# WiFan.net
KiCad netlist of a schematic drawn in Altium Designer
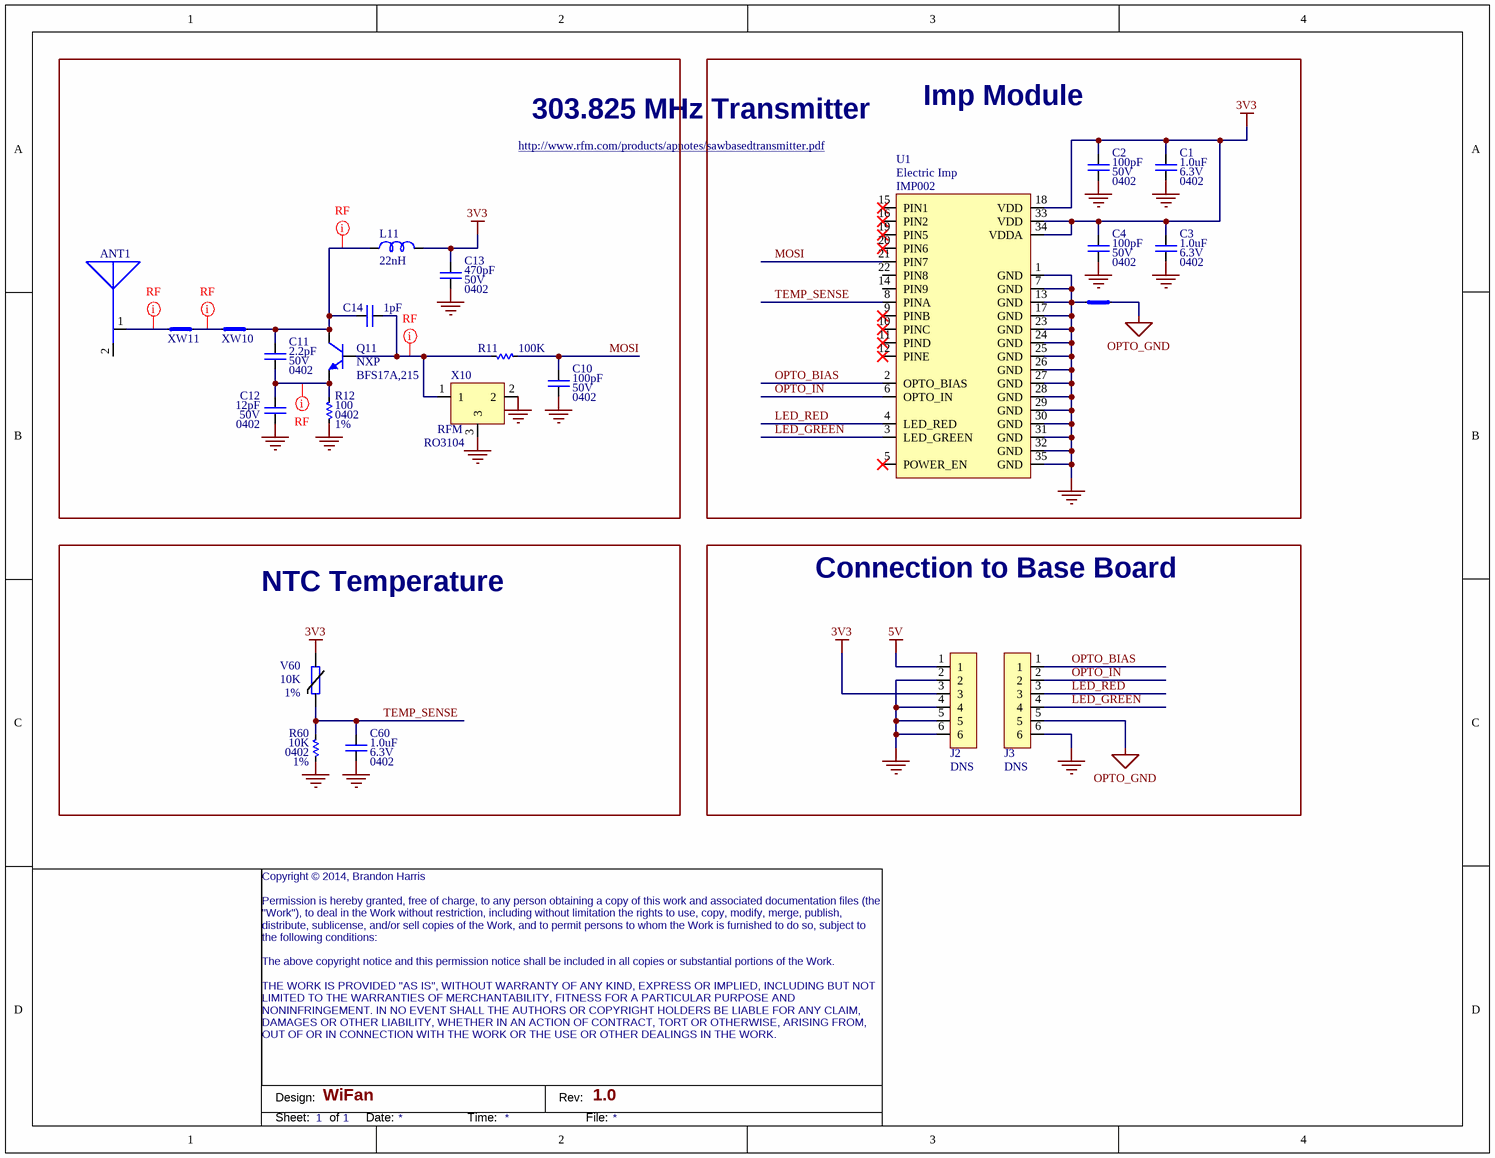
[diagram p0: WiFan.SchDoc]

(export (version "E")
  (design (tool "Eeschema 10.0.6"))
  (components
    (comp (ref "ANT1")
      (value "ANT")
      (footprint "ANT-433-HETH")
      (description "Antenna, 433 MHz, through-hole, helical, air core")
      (fields (field (name "PART NUMBER") "ANT00001") (field (name "MANUFACTURER") "Linx Technologies"))
      (libsource (lib "electromechanical") (part "ANT"))
    )
    (comp (ref "C1")
      (value "1.0uF")
      (footprint "CAPC1005X07N")
      (description "CAP,X5R,1.0uF,10%,6.3V, 0402,#")
      (fields
        (field (name "TOLERANCE") "10%")
        (field (name "VOLTAGE") "6.3V")
        (field (name "PACKAGE") "0402")
        (field (name "PART NUMBER") "CAPC00005")
      )
      (libsource (lib "passives") (part "CAPC"))
    )
    (comp (ref "C2")
      (value "100pF")
      (footprint "CAPC1005X07N")
      (description "CAP,C0G,100pF,5%,50V,0402")
      (fields
        (field (name "TOLERANCE") "5%")
        (field (name "VOLTAGE") "50V")
        (field (name "PACKAGE") "0402")
        (field (name "PART NUMBER") "CAPC00043")
      )
      (libsource (lib "passives") (part "CAPC"))
    )
    (comp (ref "C3")
      (value "1.0uF")
      (footprint "CAPC1005X07N")
      (description "CAP,X5R,1.0uF,10%,6.3V, 0402,#")
      (fields
        (field (name "TOLERANCE") "10%")
        (field (name "VOLTAGE") "6.3V")
        (field (name "PACKAGE") "0402")
        (field (name "PART NUMBER") "CAPC00005")
      )
      (libsource (lib "passives") (part "CAPC"))
    )
    (comp (ref "C4")
      (value "100pF")
      (footprint "CAPC1005X07N")
      (description "CAP,C0G,100pF,5%,50V,0402")
      (fields
        (field (name "TOLERANCE") "5%")
        (field (name "VOLTAGE") "50V")
        (field (name "PACKAGE") "0402")
        (field (name "PART NUMBER") "CAPC00043")
      )
      (libsource (lib "passives") (part "CAPC"))
    )
    (comp (ref "C10")
      (value "100pF")
      (footprint "CAPC1005X07N")
      (description "CAP,C0G,100pF,5%,50V,0402")
      (fields
        (field (name "TOLERANCE") "5%")
        (field (name "VOLTAGE") "50V")
        (field (name "PACKAGE") "0402")
        (field (name "PART NUMBER") "CAPC00043")
      )
      (libsource (lib "passives") (part "CAPC"))
    )
    (comp (ref "C11")
      (value "2.2pF")
      (footprint "CAPC1005X07N")
      (description "CAP,C0G,2.2pF,+/-0.25pF,50V,0402")
      (fields
        (field (name "TOLERANCE") "0.25p")
        (field (name "VOLTAGE") "50V")
        (field (name "PACKAGE") "0402")
        (field (name "PART NUMBER") "CAPC00080")
      )
      (libsource (lib "passives") (part "CAPC"))
    )
    (comp (ref "C12")
      (value "12pF")
      (footprint "CAPC1005X07N")
      (description "CAP,C0G,12pF,5%,50V,0402#")
      (fields
        (field (name "TOLERANCE") "5%")
        (field (name "VOLTAGE") "50V")
        (field (name "PACKAGE") "0402")
        (field (name "PART NUMBER") "CAPC00041")
      )
      (libsource (lib "passives") (part "CAPC"))
    )
    (comp (ref "C13")
      (value "470pF")
      (footprint "CAPC1005X07N")
      (description "CAP,C0G,470pF,5%,50V,0402")
      (fields
        (field (name "TOLERANCE") "5%")
        (field (name "VOLTAGE") "50V")
        (field (name "PACKAGE") "0402")
        (field (name "PART NUMBER") "CAPC00047")
      )
      (libsource (lib "passives") (part "CAPC"))
    )
    (comp (ref "C14")
      (value "1pF")
      (footprint "CAPC1005X07N")
      (description "CAP,NPO,1pF, 0402, 50V")
      (fields (field (name "TOLERANCE") "0.25p") (field (name "VOLTAGE") "50V"))
      (libsource (lib "passives") (part "CAPC"))
    )
    (comp (ref "C60")
      (value "1.0uF")
      (footprint "CAPC1005X07N")
      (description "CAP,X5R,1.0uF,10%,6.3V, 0402,#")
      (fields
        (field (name "TOLERANCE") "10%")
        (field (name "VOLTAGE") "6.3V")
        (field (name "PACKAGE") "0402")
        (field (name "PART NUMBER") "CAPC00005")
      )
      (libsource (lib "passives") (part "CAPC"))
    )
    (comp (ref "J2")
      (value "Header")
      (footprint "HDR254P1X6-N:HDR254P1X6-N")
      (description "Spacer, 1x6 Pin, 2.54mm Pitch, 0.661\" Stack Height, Vertical, Through Hole")
      (fields
        (field (name "PART NUMBER") "HDR00020")
        (field (name "MANUFACTURER") "Harwin")
        (field (name "BOMOPTION") "DNS")
      )
      (libsource (lib "discretes") (part "HDR1X6"))
    )
    (comp (ref "J3")
      (value "Header")
      (footprint "HDR254P1X6-N:HDR254P1X6-N")
      (description "Spacer, 1x6 Pin, 2.54mm Pitch, 0.661\" Stack Height, Vertical, Through Hole")
      (fields
        (field (name "PART NUMBER") "HDR00020")
        (field (name "MANUFACTURER") "Harwin")
        (field (name "BOMOPTION") "DNS")
      )
      (libsource (lib "") (part "HDR1X6_1"))
    )
    (comp (ref "L11")
      (value "22nH")
      (footprint "INDC1005X06N")
      (description "IND, 22nH, 5%, 300mA, 600 mOhm, 0402")
      (fields (field (name "PART NUMBER") "IND00036") (field (name "TOLERANCE") "5%"))
      (libsource (lib "passives") (part "INDUCTOR"))
    )
    (comp (ref "Q11")
      (value "NPN Bipolar Transistor")
      (footprint "SOT95P300X130-3N")
      (description "NPN,15V, 25mA, 2.8GHz, SOT23")
      (fields
        (field (name "PART NUMBER") "NPN00003")
        (field (name "MANUFACTURER") "NXP")
        (field (name "MANUFACTURER PART NUMBER") "BFS17A,215")
      )
      (libsource (lib "discretes") (part "NPN"))
    )
    (comp (ref "R11")
      (value "100K")
      (footprint "RESC1005X04N")
      (description "RES,100k,5%,0.063W,0402,#")
      (fields (field (name "PART NUMBER") "RES00001") (field (name "TOLERANCE") "5%"))
      (libsource (lib "passives") (part "RES"))
    )
    (comp (ref "R12")
      (value "100")
      (footprint "RESC1005X04N")
      (description "RES,100 Ohm,1%,0.063W,0402,#")
      (fields
        (field (name "PART NUMBER") "RES00024")
        (field (name "PACKAGE") "0402")
        (field (name "TOLERANCE") "1%")
        (field (name "POWER") "0.063W")
      )
      (libsource (lib "passives") (part "RES"))
    )
    (comp (ref "R60")
      (value "10K")
      (footprint "RESC1005X04N")
      (description "RES,10K,1%,0.063W,0402,#")
      (fields
        (field (name "PART NUMBER") "RES00020")
        (field (name "PACKAGE") "0402")
        (field (name "TOLERANCE") "1%")
        (field (name "POWER") "0.063W")
      )
      (libsource (lib "passives") (part "RES"))
    )
    (comp (ref "U1")
      (value "imp module")
      (footprint "IMP_MODULE")
      (description "Module, Electric Imp Solder Down with Antenna")
      (fields
        (field (name "PART NUMBER") "MOD00002")
        (field (name "MANUFACTURER") "Electric Imp")
        (field (name "MANUFACTURER PART NUMBER") "IMP002")
      )
      (libsource (lib "modules") (part "IMP_MODULE"))
    )
    (comp (ref "V60")
      (value "10K")
      (footprint "HDR1X2")
      (description "Thermistor, NTC, 10K, 1%, Radial")
      (fields
        (field (name "PART NUMBER") "NTC00008")
        (field (name "MANUFACTURER") "Murata")
        (field (name "PRECISION") "1%")
      )
      (libsource (lib "passives") (part "VARISTOR"))
    )
    (comp (ref "X10")
      (value "RESONATOR-3N")
      (footprint "TO39-3")
      (description "Resonator,SAW,303.825MHz,TO39-3")
      (fields
        (field (name "PART NUMBER") "RESONATOR00001")
        (field (name "MANUFACTURER") "RFM")
        (field (name "MANUFACTURER PART NUMBER") "RO3104")
      )
      (libsource (lib "xtalosc") (part "RESONATOR-3N"))
    )
    (comp (ref "XW1")
      (value "XW Link")
      (footprint "XW1005-COVERED")
      (description "Short two wires together")
      (fields (field (name "PART NUMBER") "ELEC00008"))
      (libsource (lib "electrical") (part "XW"))
    )
    (comp (ref "XW10")
      (value "XW Link")
      (footprint "XW1005-UNCOVERED")
      (description "Short two wires together")
      (fields (field (name "PART NUMBER") "ELEC00007"))
      (libsource (lib "electrical") (part "XW"))
    )
    (comp (ref "XW11")
      (value "XW Link")
      (footprint "XW1005-UNCOVERED")
      (description "Short two wires together")
      (fields (field (name "PART NUMBER") "ELEC00007"))
      (libsource (lib "electrical") (part "XW"))
    )
  )
  (nets
    (net (code "1") (name "/LED_GREEN") (class "Default")
      (node (ref "J3") (pin "4") (pinfunction "4_4") (pintype "passive"))
      (node (ref "U1") (pin "3") (pinfunction "LED_GREEN_3") (pintype "passive"))
    )
    (net (code "2") (name "/LED_RED") (class "Default")
      (node (ref "J3") (pin "3") (pinfunction "3_3") (pintype "passive"))
      (node (ref "U1") (pin "4") (pinfunction "LED_RED_4") (pintype "passive"))
    )
    (net (code "3") (name "/MOSI") (class "Default")
      (node (ref "C10") (pin "2") (pinfunction "2_2") (pintype "passive"))
      (node (ref "R11") (pin "1") (pinfunction "1_1") (pintype "passive"))
      (node (ref "U1") (pin "21") (pinfunction "PIN7_21") (pintype "passive"))
    )
    (net (code "4") (name "/OPTO_BIAS") (class "Default")
      (node (ref "J3") (pin "1") (pinfunction "1_1") (pintype "passive"))
      (node (ref "U1") (pin "2") (pinfunction "OPTO_BIAS_2") (pintype "passive"))
    )
    (net (code "5") (name "/OPTO_IN") (class "Default")
      (node (ref "J3") (pin "2") (pinfunction "2_2") (pintype "passive"))
      (node (ref "U1") (pin "6") (pinfunction "OPTO_IN_6") (pintype "passive"))
    )
    (net (code "6") (name "/TEMP_SENSE") (class "Default")
      (node (ref "C60") (pin "2") (pinfunction "2_2") (pintype "passive"))
      (node (ref "R60") (pin "2") (pinfunction "2_2") (pintype "passive"))
      (node (ref "U1") (pin "8") (pinfunction "PINA_8") (pintype "passive"))
      (node (ref "V60") (pin "2") (pinfunction "2_2") (pintype "passive"))
    )
    (net (code "7") (name "3V3") (class "Default")
      (node (ref "C1") (pin "2") (pinfunction "2_2") (pintype "passive"))
      (node (ref "C13") (pin "2") (pinfunction "2_2") (pintype "passive"))
      (node (ref "C2") (pin "2") (pinfunction "2_2") (pintype "passive"))
      (node (ref "C3") (pin "2") (pinfunction "2_2") (pintype "passive"))
      (node (ref "C4") (pin "2") (pinfunction "2_2") (pintype "passive"))
      (node (ref "J2") (pin "3") (pinfunction "3_3") (pintype "passive"))
      (node (ref "L11") (pin "1") (pinfunction "1_1") (pintype "passive"))
      (node (ref "U1") (pin "18") (pinfunction "VDD_18") (pintype "passive"))
      (node (ref "U1") (pin "33") (pinfunction "VDD_33") (pintype "passive"))
      (node (ref "U1") (pin "34") (pinfunction "VDDA_34") (pintype "passive"))
      (node (ref "V60") (pin "1") (pinfunction "1_1") (pintype "passive"))
    )
    (net (code "8") (name "5V") (class "Default")
      (node (ref "J2") (pin "1") (pinfunction "1_1") (pintype "passive"))
    )
    (net (code "9") (name "GND") (class "Default")
      (node (ref "C1") (pin "1") (pinfunction "1_1") (pintype "passive"))
      (node (ref "C10") (pin "1") (pinfunction "1_1") (pintype "passive"))
      (node (ref "C12") (pin "1") (pinfunction "1_1") (pintype "passive"))
      (node (ref "C13") (pin "1") (pinfunction "1_1") (pintype "passive"))
      (node (ref "C2") (pin "1") (pinfunction "1_1") (pintype "passive"))
      (node (ref "C3") (pin "1") (pinfunction "1_1") (pintype "passive"))
      (node (ref "C4") (pin "1") (pinfunction "1_1") (pintype "passive"))
      (node (ref "C60") (pin "1") (pinfunction "1_1") (pintype "passive"))
      (node (ref "J2") (pin "2") (pinfunction "2_2") (pintype "passive"))
      (node (ref "J2") (pin "4") (pinfunction "4_4") (pintype "passive"))
      (node (ref "J2") (pin "5") (pinfunction "5_5") (pintype "passive"))
      (node (ref "J2") (pin "6") (pinfunction "6_6") (pintype "passive"))
      (node (ref "J3") (pin "6") (pinfunction "6_6") (pintype "passive"))
      (node (ref "R12") (pin "1") (pinfunction "1_1") (pintype "passive"))
      (node (ref "R60") (pin "1") (pinfunction "1_1") (pintype "passive"))
      (node (ref "U1") (pin "1") (pinfunction "GND_1") (pintype "passive"))
      (node (ref "U1") (pin "13") (pinfunction "GND_13") (pintype "passive"))
      (node (ref "U1") (pin "17") (pinfunction "GND_17") (pintype "passive"))
      (node (ref "U1") (pin "23") (pinfunction "GND_23") (pintype "passive"))
      (node (ref "U1") (pin "24") (pinfunction "GND_24") (pintype "passive"))
      (node (ref "U1") (pin "25") (pinfunction "GND_25") (pintype "passive"))
      (node (ref "U1") (pin "26") (pinfunction "GND_26") (pintype "passive"))
      (node (ref "U1") (pin "27") (pinfunction "GND_27") (pintype "passive"))
      (node (ref "U1") (pin "28") (pinfunction "GND_28") (pintype "passive"))
      (node (ref "U1") (pin "29") (pinfunction "GND_29") (pintype "passive"))
      (node (ref "U1") (pin "30") (pinfunction "GND_30") (pintype "passive"))
      (node (ref "U1") (pin "31") (pinfunction "GND_31") (pintype "passive"))
      (node (ref "U1") (pin "32") (pinfunction "GND_32") (pintype "passive"))
      (node (ref "U1") (pin "35") (pinfunction "GND_35") (pintype "passive"))
      (node (ref "U1") (pin "7") (pinfunction "GND_7") (pintype "passive"))
      (node (ref "X10") (pin "2") (pinfunction "2_2") (pintype "passive"))
      (node (ref "X10") (pin "3") (pinfunction "3_3") (pintype "passive"))
      (node (ref "XW1") (pin "1") (pinfunction "1_1") (pintype "passive"))
    )
    (net (code "10") (name "Net-(ANT1-Pad1)") (class "Default")
      (node (ref "ANT1") (pin "1") (pinfunction "1_1") (pintype "passive"))
      (node (ref "XW11") (pin "2") (pinfunction "2_2") (pintype "passive"))
    )
    (net (code "11") (name "Net-(Q11-B)") (class "Default")
      (node (ref "C14") (pin "2") (pinfunction "2_2") (pintype "passive"))
      (node (ref "Q11") (pin "1") (pinfunction "B_1") (pintype "passive"))
      (node (ref "R11") (pin "2") (pinfunction "2_2") (pintype "passive"))
      (node (ref "X10") (pin "1") (pinfunction "1_1") (pintype "passive"))
    )
    (net (code "12") (name "Net-(Q11-C)") (class "Default")
      (node (ref "C11") (pin "2") (pinfunction "2_2") (pintype "passive"))
      (node (ref "C14") (pin "1") (pinfunction "1_1") (pintype "passive"))
      (node (ref "L11") (pin "2") (pinfunction "2_2") (pintype "passive"))
      (node (ref "Q11") (pin "3") (pinfunction "C_3") (pintype "passive"))
      (node (ref "XW10") (pin "1") (pinfunction "1_1") (pintype "passive"))
    )
    (net (code "13") (name "Net-(Q11-E)") (class "Default")
      (node (ref "C11") (pin "1") (pinfunction "1_1") (pintype "passive"))
      (node (ref "C12") (pin "2") (pinfunction "2_2") (pintype "passive"))
      (node (ref "Q11") (pin "2") (pinfunction "E_2") (pintype "passive"))
      (node (ref "R12") (pin "2") (pinfunction "2_2") (pintype "passive"))
    )
    (net (code "14") (name "Net-(XW10-Pad2)") (class "Default")
      (node (ref "XW10") (pin "2") (pinfunction "2_2") (pintype "passive"))
      (node (ref "XW11") (pin "1") (pinfunction "1_1") (pintype "passive"))
    )
    (net (code "15") (name "OPTO_GND") (class "Default")
      (node (ref "J3") (pin "5") (pinfunction "5_5") (pintype "passive"))
      (node (ref "XW1") (pin "2") (pinfunction "2_2") (pintype "passive"))
    )
    (net (code "16") (name "unconnected-(ANT1-Pad2)") (class "Default")
      (node (ref "ANT1") (pin "2") (pinfunction "2_2") (pintype "passive"))
    )
    (net (code "17") (name "unconnected-(U1-PIN1-Pad15)") (class "Default")
      (node (ref "U1") (pin "15") (pinfunction "PIN1_15") (pintype "passive+no_connect"))
    )
    (net (code "18") (name "unconnected-(U1-PIN2-Pad16)") (class "Default")
      (node (ref "U1") (pin "16") (pinfunction "PIN2_16") (pintype "passive+no_connect"))
    )
    (net (code "19") (name "unconnected-(U1-PIN5-Pad19)") (class "Default")
      (node (ref "U1") (pin "19") (pinfunction "PIN5_19") (pintype "passive+no_connect"))
    )
    (net (code "20") (name "unconnected-(U1-PIN6-Pad20)") (class "Default")
      (node (ref "U1") (pin "20") (pinfunction "PIN6_20") (pintype "passive+no_connect"))
    )
    (net (code "21") (name "unconnected-(U1-PIN8-Pad22)") (class "Default")
      (node (ref "U1") (pin "22") (pinfunction "PIN8_22") (pintype "passive"))
    )
    (net (code "22") (name "unconnected-(U1-PIN9-Pad14)") (class "Default")
      (node (ref "U1") (pin "14") (pinfunction "PIN9_14") (pintype "passive"))
    )
    (net (code "23") (name "unconnected-(U1-PINB-Pad9)") (class "Default")
      (node (ref "U1") (pin "9") (pinfunction "PINB_9") (pintype "passive+no_connect"))
    )
    (net (code "24") (name "unconnected-(U1-PINC-Pad10)") (class "Default")
      (node (ref "U1") (pin "10") (pinfunction "PINC_10") (pintype "passive+no_connect"))
    )
    (net (code "25") (name "unconnected-(U1-PIND-Pad11)") (class "Default")
      (node (ref "U1") (pin "11") (pinfunction "PIND_11") (pintype "passive+no_connect"))
    )
    (net (code "26") (name "unconnected-(U1-PINE-Pad12)") (class "Default")
      (node (ref "U1") (pin "12") (pinfunction "PINE_12") (pintype "passive+no_connect"))
    )
    (net (code "27") (name "unconnected-(U1-POWER_EN-Pad5)") (class "Default")
      (node (ref "U1") (pin "5") (pinfunction "POWER_EN_5") (pintype "passive+no_connect"))
    )
  )
)
